# 1u-diodeor.net
KiCad netlist of a schematic drawn in EAGLE
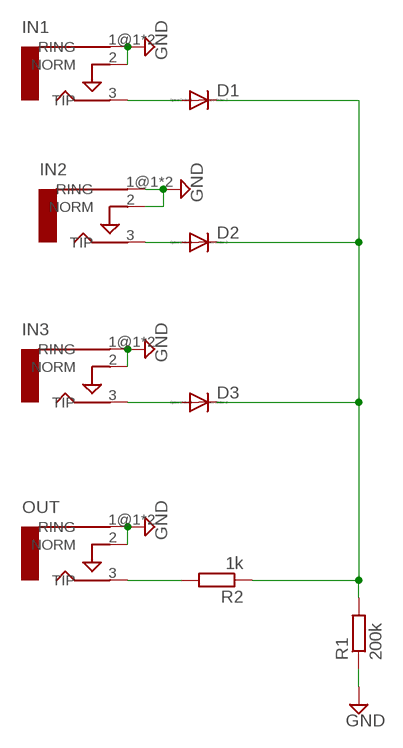
[diagram p0: schematic, sheet 1]

(export (version "E")
  (design (tool "Eeschema 10.0.6"))
  (components
    (comp (ref "D1")
      (value "DIODE-SOD123")
      (footprint "eagle-import:SOD123")
      (libsource (lib "eagle-import") (part "DIODE-SOD123"))
    )
    (comp (ref "D2")
      (value "DIODE-SOD123")
      (footprint "eagle-import:SOD123")
      (libsource (lib "eagle-import") (part "DIODE-SOD123"))
    )
    (comp (ref "D3")
      (value "DIODE-SOD123")
      (footprint "eagle-import:SOD123")
      (libsource (lib "eagle-import") (part "DIODE-SOD123"))
    )
    (comp (ref "IN1")
      (value "AUDIO-JACKERTHENVAR")
      (footprint "eagle-import:ERTHENVAR-JACK")
      (libsource (lib "eagle-import") (part "AUDIO-JACKERTHENVAR"))
    )
    (comp (ref "IN2")
      (value "AUDIO-JACKERTHENVAR")
      (footprint "eagle-import:ERTHENVAR-JACK")
      (libsource (lib "eagle-import") (part "AUDIO-JACKERTHENVAR"))
    )
    (comp (ref "IN3")
      (value "AUDIO-JACKERTHENVAR")
      (footprint "eagle-import:ERTHENVAR-JACK")
      (libsource (lib "eagle-import") (part "AUDIO-JACKERTHENVAR"))
    )
    (comp (ref "OUT")
      (value "AUDIO-JACKERTHENVAR")
      (footprint "eagle-import:ERTHENVAR-JACK")
      (libsource (lib "eagle-import") (part "AUDIO-JACKERTHENVAR"))
    )
    (comp (ref "R1")
      (value "200k")
      (footprint "eagle-import:R0805")
      (libsource (lib "eagle-import") (part "R-EU_R0805"))
    )
    (comp (ref "R2")
      (value "1k")
      (footprint "eagle-import:R0805")
      (libsource (lib "eagle-import") (part "R-EU_R0805"))
    )
  )
  (nets
    (net (code "1") (name "GND") (class "Default")
      (node (ref "IN1") (pin "1@1") (pinfunction "RING_1@1") (pintype "bidirectional"))
      (node (ref "IN1") (pin "1@2") (pinfunction "RING_1@2") (pintype "bidirectional"))
      (node (ref "IN1") (pin "2") (pinfunction "NORM_2") (pintype "bidirectional"))
      (node (ref "IN2") (pin "1@1") (pinfunction "RING_1@1") (pintype "bidirectional"))
      (node (ref "IN2") (pin "1@2") (pinfunction "RING_1@2") (pintype "bidirectional"))
      (node (ref "IN2") (pin "2") (pinfunction "NORM_2") (pintype "bidirectional"))
      (node (ref "IN3") (pin "1@1") (pinfunction "RING_1@1") (pintype "bidirectional"))
      (node (ref "IN3") (pin "1@2") (pinfunction "RING_1@2") (pintype "bidirectional"))
      (node (ref "IN3") (pin "2") (pinfunction "NORM_2") (pintype "bidirectional"))
      (node (ref "OUT") (pin "1@1") (pinfunction "RING_1@1") (pintype "bidirectional"))
      (node (ref "OUT") (pin "1@2") (pinfunction "RING_1@2") (pintype "bidirectional"))
      (node (ref "OUT") (pin "2") (pinfunction "NORM_2") (pintype "bidirectional"))
      (node (ref "R1") (pin "1") (pinfunction "1_1") (pintype "passive"))
    )
    (net (code "2") (name "Net-(D1-PadC)") (class "Default")
      (node (ref "D1") (pin "C") (pinfunction "C_C") (pintype "passive"))
      (node (ref "D2") (pin "C") (pinfunction "C_C") (pintype "passive"))
      (node (ref "D3") (pin "C") (pinfunction "C_C") (pintype "passive"))
      (node (ref "R1") (pin "2") (pinfunction "2_2") (pintype "passive"))
      (node (ref "R2") (pin "1") (pinfunction "1_1") (pintype "passive"))
    )
    (net (code "3") (name "Net-(IN1-TIP)") (class "Default")
      (node (ref "D1") (pin "A") (pinfunction "A_A") (pintype "passive"))
      (node (ref "IN1") (pin "3") (pinfunction "TIP_3") (pintype "bidirectional"))
    )
    (net (code "4") (name "Net-(IN2-TIP)") (class "Default")
      (node (ref "D2") (pin "A") (pinfunction "A_A") (pintype "passive"))
      (node (ref "IN2") (pin "3") (pinfunction "TIP_3") (pintype "bidirectional"))
    )
    (net (code "5") (name "Net-(IN3-TIP)") (class "Default")
      (node (ref "D3") (pin "A") (pinfunction "A_A") (pintype "passive"))
      (node (ref "IN3") (pin "3") (pinfunction "TIP_3") (pintype "bidirectional"))
    )
    (net (code "6") (name "Net-(OUT-TIP)") (class "Default")
      (node (ref "OUT") (pin "3") (pinfunction "TIP_3") (pintype "bidirectional"))
      (node (ref "R2") (pin "2") (pinfunction "2_2") (pintype "passive"))
    )
  )
)
